# Alimentation.net
KiCad netlist of a schematic drawn in Altium Designer
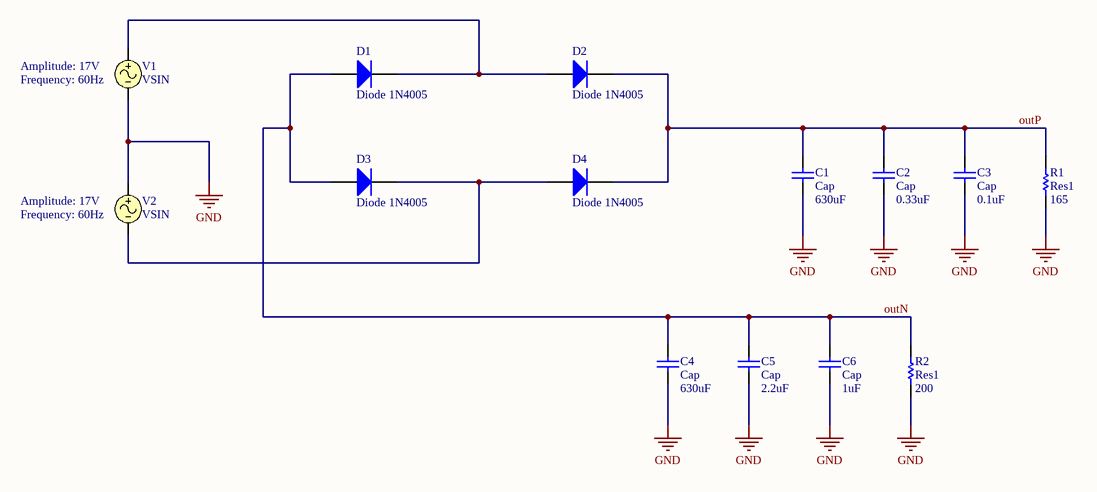
[diagram p0: Alimentation.SchDoc]

(export (version "E")
  (design (tool "Eeschema 10.0.6"))
  (components
    (comp (ref "C1")
      (value "Cap")
      (footprint "RAD-0.3")
      (description "Capacitor")
      (fields (field (name "ALTIUM_VALUE") "630uF") (field (name "PUBLISHER") "Altium Limited"))
      (libsource (lib "Miscellaneous Devices") (part "Cap"))
    )
    (comp (ref "C2")
      (value "Cap")
      (footprint "RAD-0.3")
      (description "Capacitor")
      (fields (field (name "ALTIUM_VALUE") "0.33uF") (field (name "PUBLISHER") "Altium Limited"))
      (libsource (lib "Miscellaneous Devices") (part "Cap"))
    )
    (comp (ref "C3")
      (value "Cap")
      (footprint "RAD-0.3")
      (description "Capacitor")
      (fields (field (name "ALTIUM_VALUE") "0.1uF") (field (name "PUBLISHER") "Altium Limited"))
      (libsource (lib "Miscellaneous Devices") (part "Cap"))
    )
    (comp (ref "C4")
      (value "Cap")
      (footprint "RAD-0.3")
      (description "Capacitor")
      (fields (field (name "ALTIUM_VALUE") "630uF") (field (name "PUBLISHER") "Altium Limited"))
      (libsource (lib "Miscellaneous Devices") (part "Cap"))
    )
    (comp (ref "C5")
      (value "Cap")
      (footprint "RAD-0.3")
      (description "Capacitor")
      (fields (field (name "ALTIUM_VALUE") "2.2uF") (field (name "PUBLISHER") "Altium Limited"))
      (libsource (lib "Miscellaneous Devices") (part "Cap"))
    )
    (comp (ref "C6")
      (value "Cap")
      (footprint "RAD-0.3")
      (description "Capacitor")
      (fields (field (name "ALTIUM_VALUE") "1uF") (field (name "PUBLISHER") "Altium Limited"))
      (libsource (lib "Miscellaneous Devices") (part "Cap"))
    )
    (comp (ref "D1")
      (value "Diode 1N4005")
      (footprint "DO-41")
      (description "1 Amp General Purpose Rectifier")
      (fields (field (name "PUBLISHER") "Altium Limited"))
      (libsource (lib "Miscellaneous Devices") (part "Diode 1N4005"))
    )
    (comp (ref "D2")
      (value "Diode 1N4005")
      (footprint "DO-41")
      (description "1 Amp General Purpose Rectifier")
      (fields (field (name "PUBLISHER") "Altium Limited"))
      (libsource (lib "Miscellaneous Devices") (part "Diode 1N4005"))
    )
    (comp (ref "D3")
      (value "Diode 1N4005")
      (footprint "DO-41")
      (description "1 Amp General Purpose Rectifier")
      (fields (field (name "PUBLISHER") "Altium Limited"))
      (libsource (lib "Miscellaneous Devices") (part "Diode 1N4005"))
    )
    (comp (ref "D4")
      (value "Diode 1N4005")
      (footprint "DO-41")
      (description "1 Amp General Purpose Rectifier")
      (fields (field (name "PUBLISHER") "Altium Limited"))
      (libsource (lib "Miscellaneous Devices") (part "Diode 1N4005"))
    )
    (comp (ref "R1")
      (value "Res1")
      (footprint "AXIAL-0.3")
      (description "Resistor")
      (fields (field (name "ALTIUM_VALUE") "165") (field (name "PUBLISHER") "Altium Limited"))
      (libsource (lib "Miscellaneous Devices") (part "Res1"))
    )
    (comp (ref "R2")
      (value "Res1")
      (footprint "AXIAL-0.3")
      (description "Resistor")
      (fields (field (name "ALTIUM_VALUE") "200") (field (name "PUBLISHER") "Altium Limited"))
      (libsource (lib "Miscellaneous Devices") (part "Res1"))
    )
    (comp (ref "V1")
      (value "VSIN")
      (description "Sinusoidal Voltage Source")
      (fields
        (field (name "AMPLITUDE") "17V")
        (field (name "FREQUENCY") "60Hz")
        (field (name "PUBLISHER") "Altium Limited")
      )
      (libsource (lib "Simulation Sources") (part "VSIN"))
    )
    (comp (ref "V2")
      (value "VSIN")
      (description "Sinusoidal Voltage Source")
      (fields
        (field (name "AMPLITUDE") "17V")
        (field (name "FREQUENCY") "60Hz")
        (field (name "PUBLISHER") "Altium Limited")
      )
      (libsource (lib "Simulation Sources") (part "VSIN"))
    )
  )
  (nets
    (net (code "1") (name "/outN") (class "Default")
      (node (ref "C4") (pin "2") (pinfunction "2_2") (pintype "passive"))
      (node (ref "C5") (pin "2") (pinfunction "2_2") (pintype "passive"))
      (node (ref "C6") (pin "2") (pinfunction "2_2") (pintype "passive"))
      (node (ref "D1") (pin "1") (pinfunction "A_1") (pintype "passive"))
      (node (ref "D3") (pin "1") (pinfunction "A_1") (pintype "passive"))
      (node (ref "R2") (pin "2") (pinfunction "2_2") (pintype "passive"))
    )
    (net (code "2") (name "/outP") (class "Default")
      (node (ref "C1") (pin "2") (pinfunction "2_2") (pintype "passive"))
      (node (ref "C2") (pin "2") (pinfunction "2_2") (pintype "passive"))
      (node (ref "C3") (pin "2") (pinfunction "2_2") (pintype "passive"))
      (node (ref "D2") (pin "2") (pinfunction "K_2") (pintype "passive"))
      (node (ref "D4") (pin "2") (pinfunction "K_2") (pintype "passive"))
      (node (ref "R1") (pin "2") (pinfunction "2_2") (pintype "passive"))
    )
    (net (code "3") (name "GND") (class "Default")
      (node (ref "C1") (pin "1") (pinfunction "1_1") (pintype "passive"))
      (node (ref "C2") (pin "1") (pinfunction "1_1") (pintype "passive"))
      (node (ref "C3") (pin "1") (pinfunction "1_1") (pintype "passive"))
      (node (ref "C4") (pin "1") (pinfunction "1_1") (pintype "passive"))
      (node (ref "C5") (pin "1") (pinfunction "1_1") (pintype "passive"))
      (node (ref "C6") (pin "1") (pinfunction "1_1") (pintype "passive"))
      (node (ref "R1") (pin "1") (pinfunction "1_1") (pintype "passive"))
      (node (ref "R2") (pin "1") (pinfunction "1_1") (pintype "passive"))
      (node (ref "V1") (pin "2") (pinfunction "2_2") (pintype "passive"))
      (node (ref "V2") (pin "1") (pinfunction "1_1") (pintype "passive"))
    )
    (net (code "4") (name "Net-(D1-K)") (class "Default")
      (node (ref "D1") (pin "2") (pinfunction "K_2") (pintype "passive"))
      (node (ref "D2") (pin "1") (pinfunction "A_1") (pintype "passive"))
      (node (ref "V1") (pin "1") (pinfunction "1_1") (pintype "passive"))
    )
    (net (code "5") (name "Net-(D3-K)") (class "Default")
      (node (ref "D3") (pin "2") (pinfunction "K_2") (pintype "passive"))
      (node (ref "D4") (pin "1") (pinfunction "A_1") (pintype "passive"))
      (node (ref "V2") (pin "2") (pinfunction "2_2") (pintype "passive"))
    )
  )
)
